# Reciever_11-16.net
KiCad netlist of a schematic drawn in EAGLE
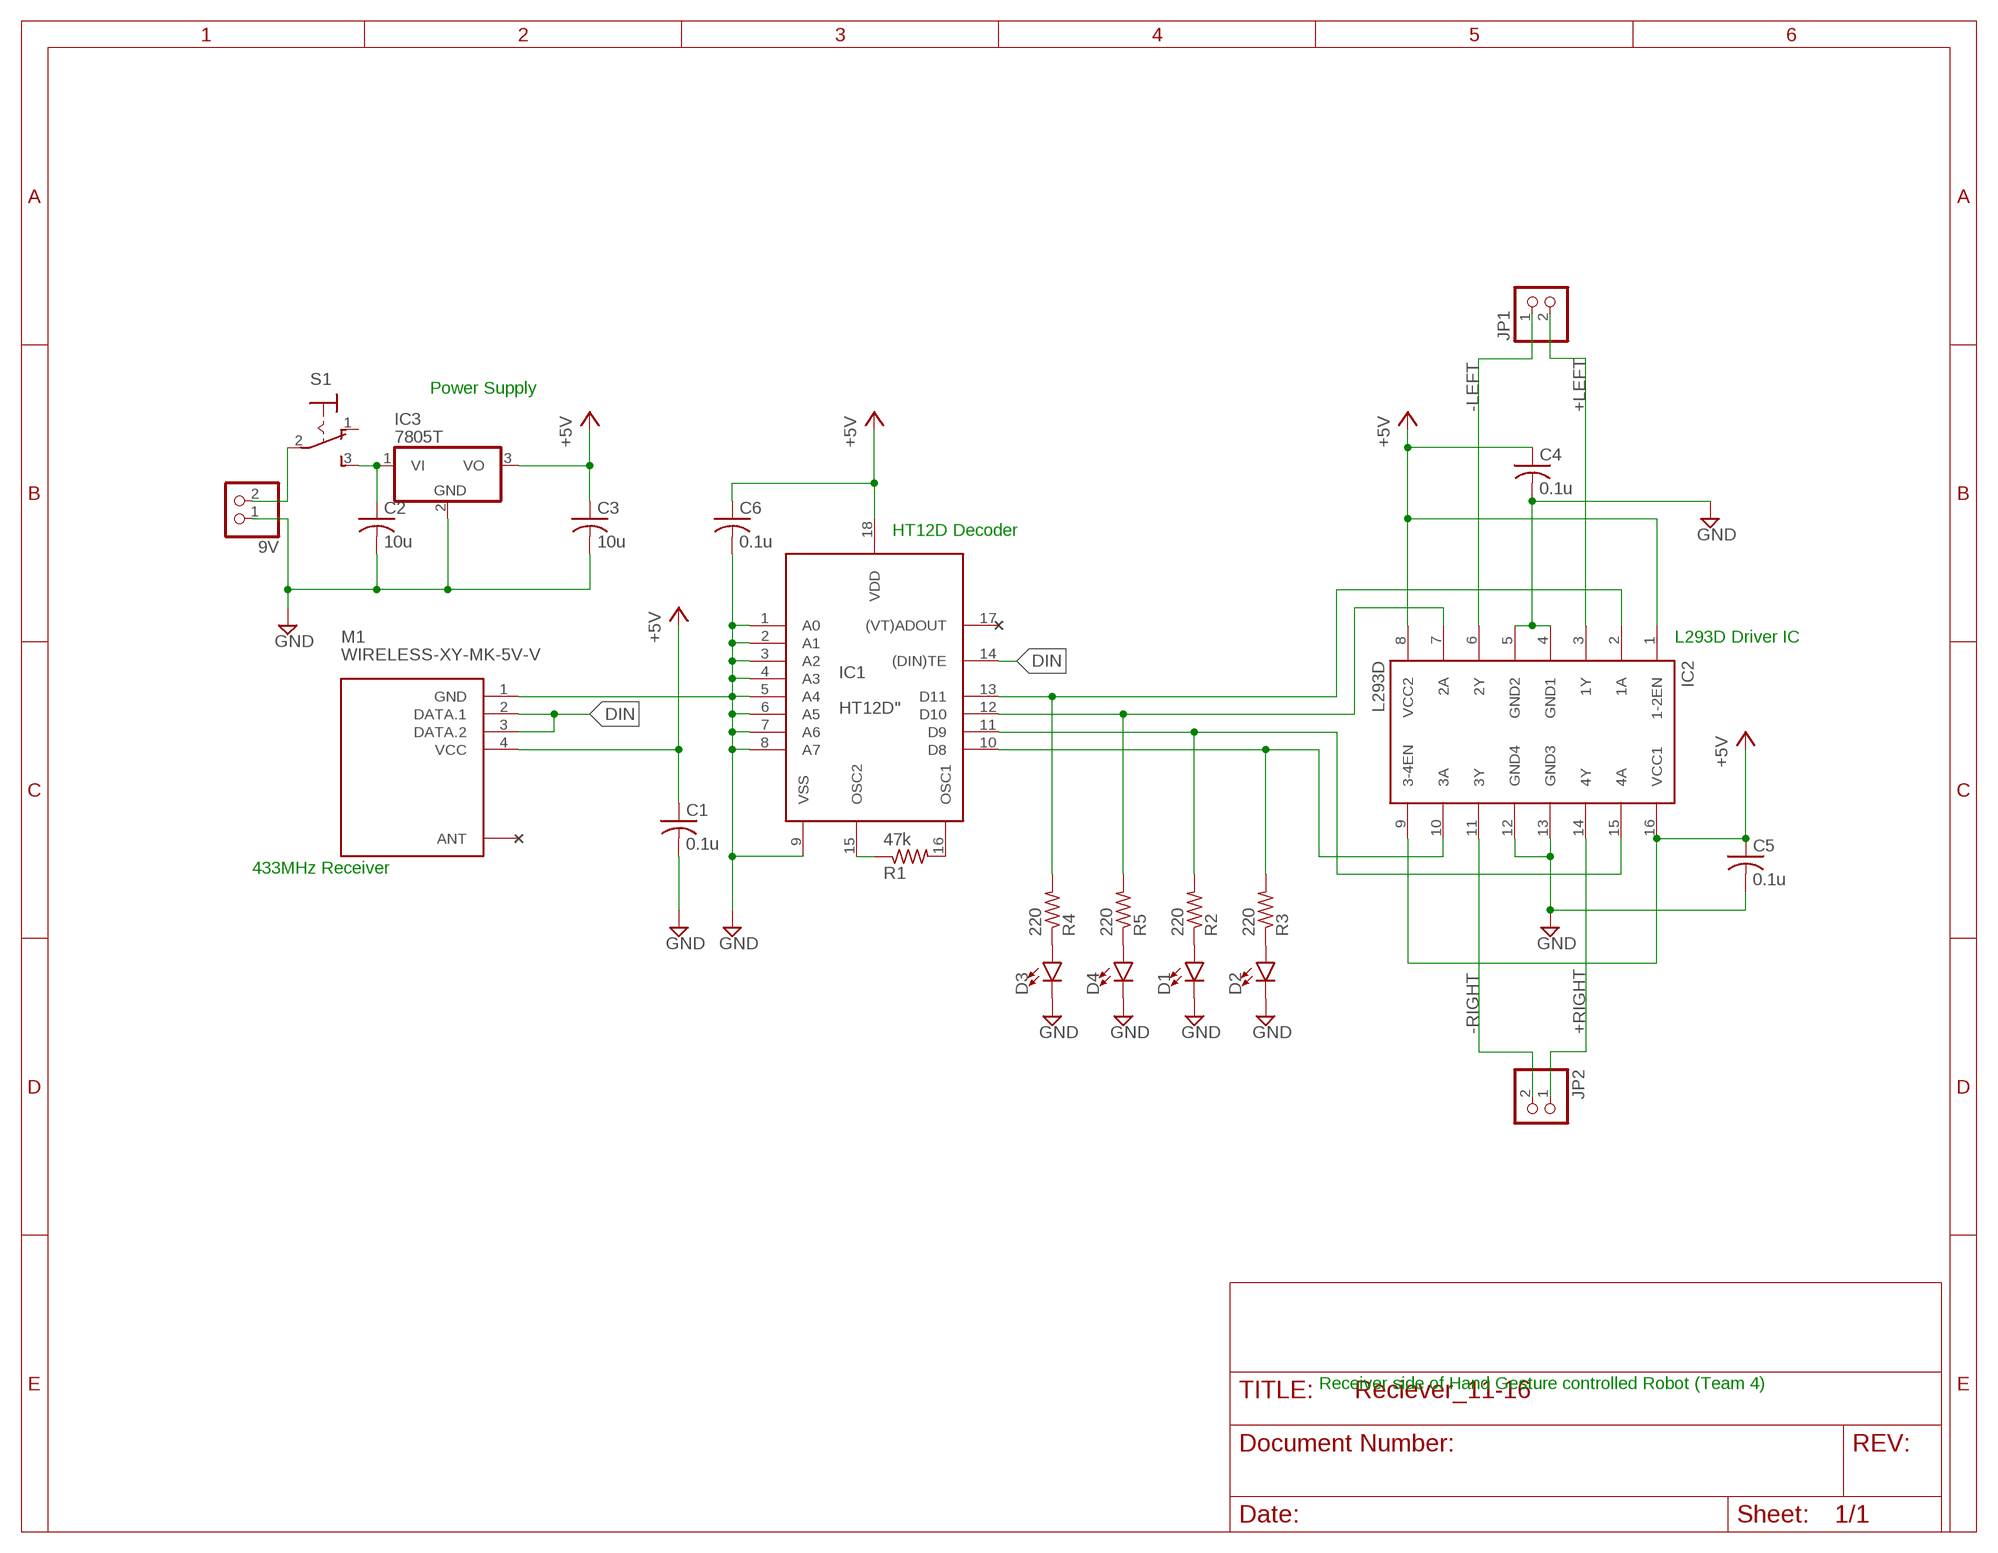
[diagram p0: schematic, sheet 1]

(export (version "E")
  (design (tool "Eeschema 10.0.6"))
  (components
    (comp (ref "9V")
      (value "PINHD-1X2")
      (footprint "eagle-import:1X02")
      (libsource (lib "eagle-import") (part "PINHD-1X2"))
    )
    (comp (ref "C1")
      (value "0.1u")
      (footprint "eagle-import:C0805")
      (libsource (lib "eagle-import") (part "C-USC0805"))
    )
    (comp (ref "C2")
      (value "10u")
      (footprint "eagle-import:C0805")
      (libsource (lib "eagle-import") (part "C-USC0805"))
    )
    (comp (ref "C3")
      (value "10u")
      (footprint "eagle-import:C0805")
      (libsource (lib "eagle-import") (part "C-USC0805"))
    )
    (comp (ref "C4")
      (value "0.1u")
      (footprint "eagle-import:C0805")
      (libsource (lib "eagle-import") (part "C-USC0805"))
    )
    (comp (ref "C5")
      (value "0.1u")
      (footprint "eagle-import:C0805")
      (libsource (lib "eagle-import") (part "C-USC0805"))
    )
    (comp (ref "C6")
      (value "0.1u")
      (footprint "eagle-import:C0805")
      (libsource (lib "eagle-import") (part "C-USC0805"))
    )
    (comp (ref "D1")
      (value "LED3MM")
      (footprint "eagle-import:LED_3MM")
      (libsource (lib "eagle-import") (part "LED3MM"))
    )
    (comp (ref "D2")
      (value "LED3MM")
      (footprint "eagle-import:LED_3MM")
      (libsource (lib "eagle-import") (part "LED3MM"))
    )
    (comp (ref "D3")
      (value "LED3MM")
      (footprint "eagle-import:LED_3MM")
      (libsource (lib "eagle-import") (part "LED3MM"))
    )
    (comp (ref "D4")
      (value "LED3MM")
      (footprint "eagle-import:LED_3MM")
      (libsource (lib "eagle-import") (part "LED3MM"))
    )
    (comp (ref "IC1")
      (value "HT12D\"")
      (footprint "eagle-import:18-DIP-A")
      (libsource (lib "eagle-import") (part "HT12D{dblquote}"))
    )
    (comp (ref "IC2")
      (value "L293D")
      (footprint "eagle-import:DIL16")
      (libsource (lib "eagle-import") (part "L293D"))
    )
    (comp (ref "IC3")
      (value "7805T")
      (footprint "eagle-import:TO220H")
      (libsource (lib "eagle-import") (part "78T05"))
    )
    (comp (ref "JP1")
      (value "PINHD-1X2")
      (footprint "eagle-import:1X02")
      (libsource (lib "eagle-import") (part "PINHD-1X2"))
    )
    (comp (ref "JP2")
      (value "PINHD-1X2")
      (footprint "eagle-import:1X02")
      (libsource (lib "eagle-import") (part "PINHD-1X2"))
    )
    (comp (ref "M1")
      (value "WIRELESS-XY-MK-5V-V")
      (footprint "eagle-import:WIRELESS-XY-MK-5V#V")
      (libsource (lib "eagle-import") (part "WIRELESS-XY-MK-5V-V"))
    )
    (comp (ref "R1")
      (value "47k")
      (footprint "eagle-import:R0805")
      (libsource (lib "eagle-import") (part "R-US_R0805"))
    )
    (comp (ref "R2")
      (value "220")
      (footprint "eagle-import:R0805")
      (libsource (lib "eagle-import") (part "R-US_R0805"))
    )
    (comp (ref "R3")
      (value "220")
      (footprint "eagle-import:R0805")
      (libsource (lib "eagle-import") (part "R-US_R0805"))
    )
    (comp (ref "R4")
      (value "220")
      (footprint "eagle-import:R0805")
      (libsource (lib "eagle-import") (part "R-US_R0805"))
    )
    (comp (ref "R5")
      (value "220")
      (footprint "eagle-import:R0805")
      (libsource (lib "eagle-import") (part "R-US_R0805"))
    )
    (comp (ref "S1")
      (value "M9040P")
      (footprint "eagle-import:M9040P")
      (libsource (lib "eagle-import") (part "M9040P"))
    )
  )
  (nets
    (net (code "1") (name "+5V") (class "Default")
      (node (ref "C1") (pin "1") (pinfunction "1_1") (pintype "passive"))
      (node (ref "C3") (pin "1") (pinfunction "1_1") (pintype "passive"))
      (node (ref "C4") (pin "1") (pinfunction "1_1") (pintype "passive"))
      (node (ref "C5") (pin "1") (pinfunction "1_1") (pintype "passive"))
      (node (ref "C6") (pin "1") (pinfunction "1_1") (pintype "passive"))
      (node (ref "IC1") (pin "18") (pinfunction "VDD_18") (pintype "power_in"))
      (node (ref "IC2") (pin "1") (pinfunction "1-2EN_1") (pintype "input"))
      (node (ref "IC2") (pin "16") (pinfunction "VCC1_16") (pintype "power_in"))
      (node (ref "IC2") (pin "8") (pinfunction "VCC2_8") (pintype "power_in"))
      (node (ref "IC2") (pin "9") (pinfunction "3-4EN_9") (pintype "input"))
      (node (ref "IC3") (pin "3") (pinfunction "VO_3") (pintype "passive"))
      (node (ref "M1") (pin "4") (pinfunction "VCC_4") (pintype "bidirectional"))
    )
    (net (code "2") (name "/+LEFT") (class "Default")
      (node (ref "IC2") (pin "3") (pinfunction "1Y_3") (pintype "output"))
      (node (ref "JP1") (pin "2") (pinfunction "2_2") (pintype "passive"))
    )
    (net (code "3") (name "/+RIGHT") (class "Default")
      (node (ref "IC2") (pin "14") (pinfunction "4Y_14") (pintype "output"))
      (node (ref "JP2") (pin "1") (pinfunction "1_1") (pintype "passive"))
    )
    (net (code "4") (name "/-LEFT") (class "Default")
      (node (ref "IC2") (pin "6") (pinfunction "2Y_6") (pintype "output"))
      (node (ref "JP1") (pin "1") (pinfunction "1_1") (pintype "passive"))
    )
    (net (code "5") (name "/-RIGHT") (class "Default")
      (node (ref "IC2") (pin "11") (pinfunction "3Y_11") (pintype "output"))
      (node (ref "JP2") (pin "2") (pinfunction "2_2") (pintype "passive"))
    )
    (net (code "6") (name "DIN") (class "Default")
      (node (ref "IC1") (pin "14") (pinfunction "(DIN)TE_14") (pintype "input"))
      (node (ref "M1") (pin "2") (pinfunction "DATA.1_2") (pintype "bidirectional"))
      (node (ref "M1") (pin "3") (pinfunction "DATA.2_3") (pintype "bidirectional"))
    )
    (net (code "7") (name "GND") (class "Default")
      (node (ref "9V") (pin "1") (pinfunction "1_1") (pintype "passive"))
      (node (ref "C1") (pin "2") (pinfunction "2_2") (pintype "passive"))
      (node (ref "C2") (pin "2") (pinfunction "2_2") (pintype "passive"))
      (node (ref "C3") (pin "2") (pinfunction "2_2") (pintype "passive"))
      (node (ref "C4") (pin "2") (pinfunction "2_2") (pintype "passive"))
      (node (ref "C5") (pin "2") (pinfunction "2_2") (pintype "passive"))
      (node (ref "C6") (pin "2") (pinfunction "2_2") (pintype "passive"))
      (node (ref "D1") (pin "K") (pinfunction "C_K") (pintype "passive"))
      (node (ref "D2") (pin "K") (pinfunction "C_K") (pintype "passive"))
      (node (ref "D3") (pin "K") (pinfunction "C_K") (pintype "passive"))
      (node (ref "D4") (pin "K") (pinfunction "C_K") (pintype "passive"))
      (node (ref "IC1") (pin "1") (pinfunction "A0_1") (pintype "input"))
      (node (ref "IC1") (pin "2") (pinfunction "A1_2") (pintype "input"))
      (node (ref "IC1") (pin "3") (pinfunction "A2_3") (pintype "input"))
      (node (ref "IC1") (pin "4") (pinfunction "A3_4") (pintype "input"))
      (node (ref "IC1") (pin "5") (pinfunction "A4_5") (pintype "input"))
      (node (ref "IC1") (pin "6") (pinfunction "A5_6") (pintype "input"))
      (node (ref "IC1") (pin "7") (pinfunction "A6_7") (pintype "input"))
      (node (ref "IC1") (pin "8") (pinfunction "A7_8") (pintype "input"))
      (node (ref "IC1") (pin "9") (pinfunction "VSS_9") (pintype "power_in"))
      (node (ref "IC2") (pin "12") (pinfunction "GND4_12") (pintype "power_in"))
      (node (ref "IC2") (pin "13") (pinfunction "GND3_13") (pintype "power_in"))
      (node (ref "IC2") (pin "4") (pinfunction "GND1_4") (pintype "power_in"))
      (node (ref "IC2") (pin "5") (pinfunction "GND2_5") (pintype "power_in"))
      (node (ref "IC3") (pin "2") (pinfunction "GND_2") (pintype "passive"))
      (node (ref "M1") (pin "1") (pinfunction "GND_1") (pintype "bidirectional"))
    )
    (net (code "8") (name "Net-(D1-PadA)") (class "Default")
      (node (ref "D1") (pin "A") (pinfunction "A_A") (pintype "passive"))
      (node (ref "R2") (pin "1") (pinfunction "1_1") (pintype "passive"))
    )
    (net (code "9") (name "Net-(D2-PadA)") (class "Default")
      (node (ref "D2") (pin "A") (pinfunction "A_A") (pintype "passive"))
      (node (ref "R3") (pin "1") (pinfunction "1_1") (pintype "passive"))
    )
    (net (code "10") (name "Net-(D3-PadA)") (class "Default")
      (node (ref "D3") (pin "A") (pinfunction "A_A") (pintype "passive"))
      (node (ref "R4") (pin "1") (pinfunction "1_1") (pintype "passive"))
    )
    (net (code "11") (name "Net-(D4-PadA)") (class "Default")
      (node (ref "D4") (pin "A") (pinfunction "A_A") (pintype "passive"))
      (node (ref "R5") (pin "1") (pinfunction "1_1") (pintype "passive"))
    )
    (net (code "12") (name "Net-(IC1-D8)") (class "Default")
      (node (ref "IC1") (pin "10") (pinfunction "D8_10") (pintype "output"))
      (node (ref "IC2") (pin "10") (pinfunction "3A_10") (pintype "input"))
      (node (ref "R3") (pin "2") (pinfunction "2_2") (pintype "passive"))
    )
    (net (code "13") (name "Net-(IC1-D9)") (class "Default")
      (node (ref "IC1") (pin "11") (pinfunction "D9_11") (pintype "output"))
      (node (ref "IC2") (pin "15") (pinfunction "4A_15") (pintype "input"))
      (node (ref "R2") (pin "2") (pinfunction "2_2") (pintype "passive"))
    )
    (net (code "14") (name "Net-(IC1-D10)") (class "Default")
      (node (ref "IC1") (pin "12") (pinfunction "D10_12") (pintype "output"))
      (node (ref "IC2") (pin "7") (pinfunction "2A_7") (pintype "input"))
      (node (ref "R5") (pin "2") (pinfunction "2_2") (pintype "passive"))
    )
    (net (code "15") (name "Net-(IC1-D11)") (class "Default")
      (node (ref "IC1") (pin "13") (pinfunction "D11_13") (pintype "output"))
      (node (ref "IC2") (pin "2") (pinfunction "1A_2") (pintype "input"))
      (node (ref "R4") (pin "2") (pinfunction "2_2") (pintype "passive"))
    )
    (net (code "16") (name "Net-(IC1-OSC1)") (class "Default")
      (node (ref "IC1") (pin "16") (pinfunction "OSC1_16") (pintype "input"))
      (node (ref "R1") (pin "2") (pinfunction "2_2") (pintype "passive"))
    )
    (net (code "17") (name "Net-(IC1-OSC2)") (class "Default")
      (node (ref "IC1") (pin "15") (pinfunction "OSC2_15") (pintype "output"))
      (node (ref "R1") (pin "1") (pinfunction "1_1") (pintype "passive"))
    )
    (net (code "18") (name "Net-(IC3-VI)") (class "Default")
      (node (ref "C2") (pin "1") (pinfunction "1_1") (pintype "passive"))
      (node (ref "IC3") (pin "1") (pinfunction "VI_1") (pintype "input"))
      (node (ref "S1") (pin "3") (pinfunction "S_3") (pintype "passive"))
    )
    (net (code "19") (name "Net-(S1-P)") (class "Default")
      (node (ref "9V") (pin "2") (pinfunction "2_2") (pintype "passive"))
      (node (ref "S1") (pin "2") (pinfunction "P_2") (pintype "passive"))
    )
    (net (code "20") (name "unconnected-(IC1-(VT)ADOUT-Pad17)") (class "Default")
      (node (ref "IC1") (pin "17") (pinfunction "(VT)ADOUT_17") (pintype "output"))
    )
    (net (code "21") (name "unconnected-(M1-PadANT)") (class "Default")
      (node (ref "M1") (pin "ANT") (pinfunction "ANT_ANT") (pintype "output"))
    )
    (net (code "22") (name "unconnected-(S1-O-Pad1)") (class "Default")
      (node (ref "S1") (pin "1") (pinfunction "O_1") (pintype "passive"))
    )
  )
)
